# Ebook_Anita_Ghita.net
KiCad netlist of a schematic drawn in EAGLE
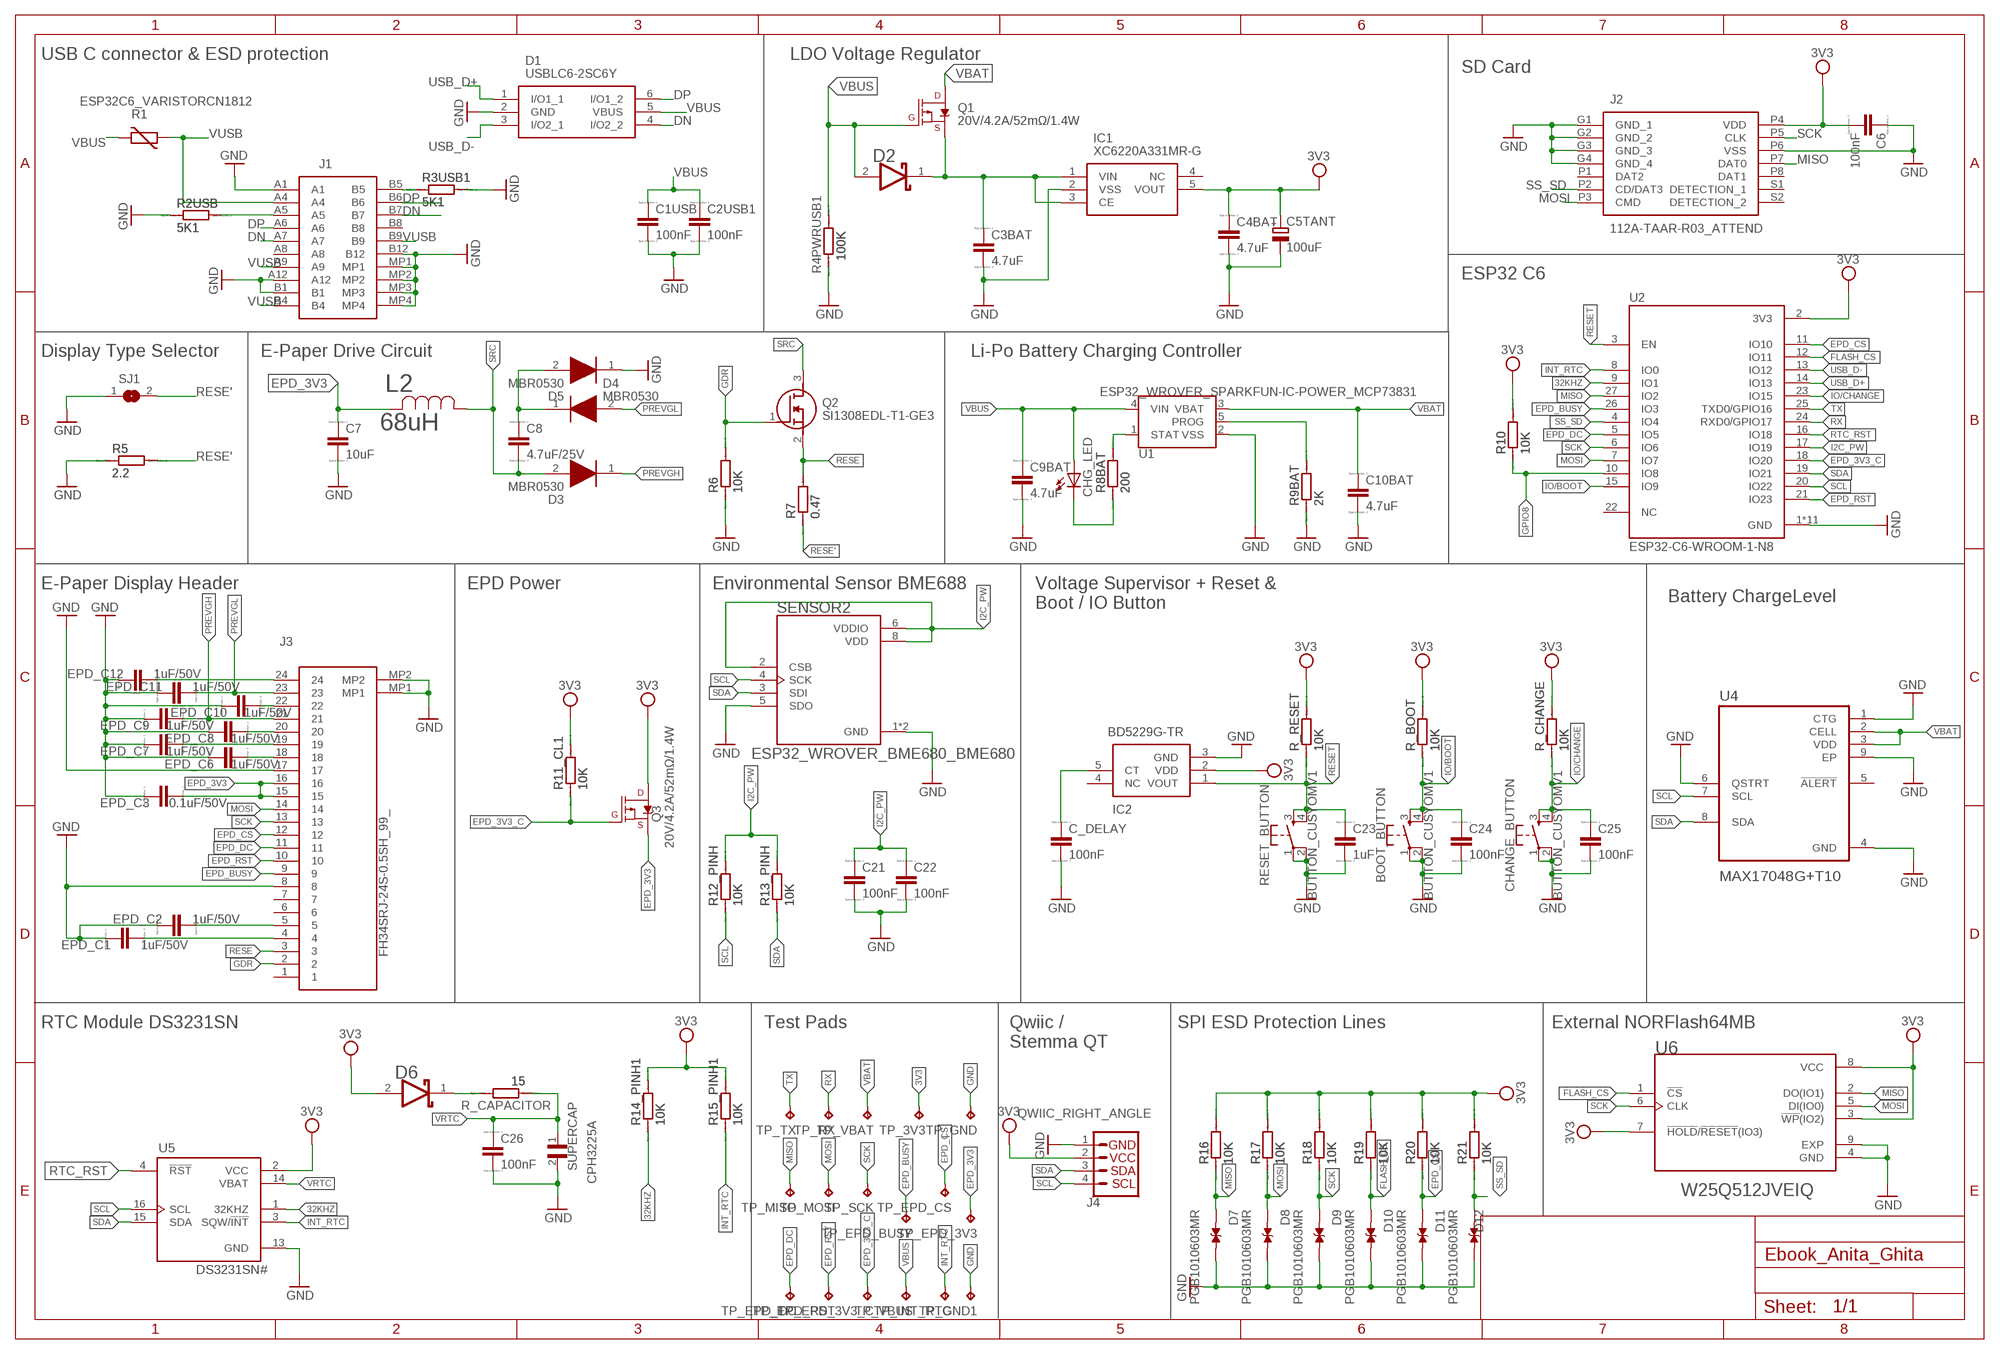
[diagram p0: schematic, sheet 1]

(export (version "E")
  (design (tool "Eeschema 10.0.6"))
  (components
    (comp (ref "BOOT_BUTTON")
      (value "BUTTON_CUSYOMV1")
      (footprint "eagle-import:MYBUTTON")
      (libsource (lib "eagle-import") (part "BUTTON_CUSYOMV1"))
    )
    (comp (ref "C1USB")
      (value "100nF")
      (footprint "eagle-import:ESP32_WROVER_EAGLE-LTSPICE_C0402")
      (libsource (lib "eagle-import") (part "EAGLE-LTSPICE_CC0402"))
    )
    (comp (ref "C2USB1")
      (value "100nF")
      (footprint "eagle-import:ESP32_WROVER_EAGLE-LTSPICE_C0402")
      (libsource (lib "eagle-import") (part "EAGLE-LTSPICE_CC0402"))
    )
    (comp (ref "C3BAT")
      (value "4.7uF")
      (footprint "eagle-import:ESP32_WROVER_EAGLE-LTSPICE_C0402")
      (libsource (lib "eagle-import") (part "EAGLE-LTSPICE_CC0402"))
    )
    (comp (ref "C4BAT")
      (value "4.7uF")
      (footprint "eagle-import:ESP32_WROVER_EAGLE-LTSPICE_C0402")
      (libsource (lib "eagle-import") (part "EAGLE-LTSPICE_CC0402"))
    )
    (comp (ref "C5TANT")
      (value "100uF")
      (footprint "eagle-import:RCL_CT3528")
      (libsource (lib "eagle-import") (part "RCL_CPOL-EUCT3528"))
    )
    (comp (ref "C6")
      (value "100nF")
      (footprint "eagle-import:ESP32_WROVER_EAGLE-LTSPICE_C0402")
      (libsource (lib "eagle-import") (part "EAGLE-LTSPICE_CC0402"))
    )
    (comp (ref "C7")
      (value "10uF")
      (footprint "eagle-import:ESP32_WROVER_EAGLE-LTSPICE_C0402")
      (libsource (lib "eagle-import") (part "EAGLE-LTSPICE_CC0402"))
    )
    (comp (ref "C8")
      (value "4.7uF/25V")
      (footprint "eagle-import:ESP32_WROVER_EAGLE-LTSPICE_C0402")
      (libsource (lib "eagle-import") (part "EAGLE-LTSPICE_CC0402"))
    )
    (comp (ref "C9BAT")
      (value "4.7uF")
      (footprint "eagle-import:ESP32_WROVER_EAGLE-LTSPICE_C0402")
      (libsource (lib "eagle-import") (part "EAGLE-LTSPICE_CC0402"))
    )
    (comp (ref "C10BAT")
      (value "4.7uF")
      (footprint "eagle-import:ESP32_WROVER_EAGLE-LTSPICE_C0402")
      (libsource (lib "eagle-import") (part "EAGLE-LTSPICE_CC0402"))
    )
    (comp (ref "C21")
      (value "100nF")
      (footprint "eagle-import:ESP32_WROVER_EAGLE-LTSPICE_C0402")
      (libsource (lib "eagle-import") (part "EAGLE-LTSPICE_CC0402"))
    )
    (comp (ref "C22")
      (value "100nF")
      (footprint "eagle-import:ESP32_WROVER_EAGLE-LTSPICE_C0402")
      (libsource (lib "eagle-import") (part "EAGLE-LTSPICE_CC0402"))
    )
    (comp (ref "C23")
      (value "1uF")
      (footprint "eagle-import:ESP32_WROVER_EAGLE-LTSPICE_C0402")
      (libsource (lib "eagle-import") (part "EAGLE-LTSPICE_CC0402"))
    )
    (comp (ref "C24")
      (value "100nF")
      (footprint "eagle-import:ESP32_WROVER_EAGLE-LTSPICE_C0402")
      (libsource (lib "eagle-import") (part "EAGLE-LTSPICE_CC0402"))
    )
    (comp (ref "C25")
      (value "100nF")
      (footprint "eagle-import:ESP32_WROVER_EAGLE-LTSPICE_C0402")
      (libsource (lib "eagle-import") (part "EAGLE-LTSPICE_CC0402"))
    )
    (comp (ref "C26")
      (value "100nF")
      (footprint "eagle-import:ESP32_WROVER_EAGLE-LTSPICE_C0402")
      (libsource (lib "eagle-import") (part "EAGLE-LTSPICE_CC0402"))
    )
    (comp (ref "CHANGE_BUTTON")
      (value "BUTTON_CUSYOMV1")
      (footprint "eagle-import:MYBUTTON")
      (libsource (lib "eagle-import") (part "BUTTON_CUSYOMV1"))
    )
    (comp (ref "CHG_LED")
      (value "ADAFRUIT_LEDCHIP-LED0603")
      (footprint "eagle-import:ADAFRUIT_CHIP-LED0603")
      (libsource (lib "eagle-import") (part "ADAFRUIT_LEDCHIP-LED0603"))
    )
    (comp (ref "C_DELAY")
      (value "100nF")
      (footprint "eagle-import:ESP32_WROVER_EAGLE-LTSPICE_C0402")
      (libsource (lib "eagle-import") (part "EAGLE-LTSPICE_CC0402"))
    )
    (comp (ref "D1")
      (value "USBLC6-2SC6Y")
      (footprint "eagle-import:SOT95P280X145-6N")
      (fields (field (name "MF") "STMicroelectronics"))
      (libsource (lib "eagle-import") (part "USBLC6-2SC6Y"))
    )
    (comp (ref "D2")
      (value "ESP32_WROVER_AVX---SD0805S020S1R0_AVX_SD0805S020S1R0_0_0AVX_SD0805S020S1R0_0_0")
      (footprint "eagle-import:ESP32_WROVER_AVX---SD0805S020S1R0_AVX_SD0805S020S1R0_0")
      (fields
        (field (name "DIGIKEY_PART_NUMBER") "478-7800-1-ND")
        (field (name "MF") "AVX")
        (field (name "MOUSER_PART_NUMBER") "581-SD0805S020S1R0")
      )
      (libsource (lib "eagle-import") (part "ESP32_WROVER_AVX---SD0805S020S1R0_AVX_SD0805S020S1R0_0_0AVX_SD0805S020S1R0_0_0"))
    )
    (comp (ref "D3")
      (value "MBR0530")
      (footprint "eagle-import:SOD3716X135N")
      (fields (field (name "MF") "ON Semiconductor"))
      (libsource (lib "eagle-import") (part "MBR0530"))
    )
    (comp (ref "D4")
      (value "MBR0530")
      (footprint "eagle-import:SOD3716X135N")
      (fields (field (name "MF") "ON Semiconductor"))
      (libsource (lib "eagle-import") (part "MBR0530"))
    )
    (comp (ref "D5")
      (value "MBR0530")
      (footprint "eagle-import:SOD3716X135N")
      (fields (field (name "MF") "ON Semiconductor"))
      (libsource (lib "eagle-import") (part "MBR0530"))
    )
    (comp (ref "D6")
      (value "ESP32_WROVER_AVX---SD0805S020S1R0_AVX_SD0805S020S1R0_0_0AVX_SD0805S020S1R0_0_0")
      (footprint "eagle-import:ESP32_WROVER_AVX---SD0805S020S1R0_AVX_SD0805S020S1R0_0")
      (fields
        (field (name "DIGIKEY_PART_NUMBER") "478-7800-1-ND")
        (field (name "MF") "AVX")
        (field (name "MOUSER_PART_NUMBER") "581-SD0805S020S1R0")
      )
      (libsource (lib "eagle-import") (part "ESP32_WROVER_AVX---SD0805S020S1R0_AVX_SD0805S020S1R0_0_0AVX_SD0805S020S1R0_0_0"))
    )
    (comp (ref "D7")
      (value "PGB1010603MR")
      (footprint "eagle-import:DIOC1608X36N")
      (fields (field (name "MF") "Littelfuse Inc."))
      (libsource (lib "eagle-import") (part "PGB1010603MR"))
    )
    (comp (ref "D8")
      (value "PGB1010603MR")
      (footprint "eagle-import:DIOC1608X36N")
      (fields (field (name "MF") "Littelfuse Inc."))
      (libsource (lib "eagle-import") (part "PGB1010603MR"))
    )
    (comp (ref "D9")
      (value "PGB1010603MR")
      (footprint "eagle-import:DIOC1608X36N")
      (fields (field (name "MF") "Littelfuse Inc."))
      (libsource (lib "eagle-import") (part "PGB1010603MR"))
    )
    (comp (ref "D10")
      (value "PGB1010603MR")
      (footprint "eagle-import:DIOC1608X36N")
      (fields (field (name "MF") "Littelfuse Inc."))
      (libsource (lib "eagle-import") (part "PGB1010603MR"))
    )
    (comp (ref "D11")
      (value "PGB1010603MR")
      (footprint "eagle-import:DIOC1608X36N")
      (fields (field (name "MF") "Littelfuse Inc."))
      (libsource (lib "eagle-import") (part "PGB1010603MR"))
    )
    (comp (ref "D12")
      (value "PGB1010603MR")
      (footprint "eagle-import:DIOC1608X36N")
      (fields (field (name "MF") "Littelfuse Inc."))
      (libsource (lib "eagle-import") (part "PGB1010603MR"))
    )
    (comp (ref "EPD_C1")
      (value "1uF/50V")
      (footprint "eagle-import:ESP32_WROVER_EAGLE-LTSPICE_C0402")
      (libsource (lib "eagle-import") (part "EAGLE-LTSPICE_CC0402"))
    )
    (comp (ref "EPD_C2")
      (value "1uF/50V")
      (footprint "eagle-import:ESP32_WROVER_EAGLE-LTSPICE_C0402")
      (libsource (lib "eagle-import") (part "EAGLE-LTSPICE_CC0402"))
    )
    (comp (ref "EPD_C3")
      (value "0.1uF/50V")
      (footprint "eagle-import:ESP32_WROVER_EAGLE-LTSPICE_C0402")
      (libsource (lib "eagle-import") (part "EAGLE-LTSPICE_CC0402"))
    )
    (comp (ref "EPD_C6")
      (value "1uF/50V")
      (footprint "eagle-import:ESP32_WROVER_EAGLE-LTSPICE_C0402")
      (libsource (lib "eagle-import") (part "EAGLE-LTSPICE_CC0402"))
    )
    (comp (ref "EPD_C7")
      (value "1uF/50V")
      (footprint "eagle-import:ESP32_WROVER_EAGLE-LTSPICE_C0402")
      (libsource (lib "eagle-import") (part "EAGLE-LTSPICE_CC0402"))
    )
    (comp (ref "EPD_C8")
      (value "1uF/50V")
      (footprint "eagle-import:ESP32_WROVER_EAGLE-LTSPICE_C0402")
      (libsource (lib "eagle-import") (part "EAGLE-LTSPICE_CC0402"))
    )
    (comp (ref "EPD_C9")
      (value "1uF/50V")
      (footprint "eagle-import:ESP32_WROVER_EAGLE-LTSPICE_C0402")
      (libsource (lib "eagle-import") (part "EAGLE-LTSPICE_CC0402"))
    )
    (comp (ref "EPD_C10")
      (value "1uF/50V")
      (footprint "eagle-import:ESP32_WROVER_EAGLE-LTSPICE_C0402")
      (libsource (lib "eagle-import") (part "EAGLE-LTSPICE_CC0402"))
    )
    (comp (ref "EPD_C11")
      (value "1uF/50V")
      (footprint "eagle-import:ESP32_WROVER_EAGLE-LTSPICE_C0402")
      (libsource (lib "eagle-import") (part "EAGLE-LTSPICE_CC0402"))
    )
    (comp (ref "EPD_C12")
      (value "1uF/50V")
      (footprint "eagle-import:ESP32_WROVER_EAGLE-LTSPICE_C0402")
      (libsource (lib "eagle-import") (part "EAGLE-LTSPICE_CC0402"))
    )
    (comp (ref "IC1")
      (value "XC6220A331MR-G")
      (footprint "eagle-import:SOT95P280X120-5N")
      (fields (field (name "MOUSER_PART_NUMBER") "865-XC6220A331MR-G"))
      (libsource (lib "eagle-import") (part "XC6220A331MR-G"))
    )
    (comp (ref "IC2")
      (value "BD5229G-TR")
      (footprint "eagle-import:SOT95P280X125-5N")
      (fields (field (name "MOUSER_PART_NUMBER") "755-BD5229G-TR"))
      (libsource (lib "eagle-import") (part "BD5229G-TR"))
    )
    (comp (ref "J1")
      (value "SAMACSYS_PARTS_USB4110-GF-A")
      (footprint "eagle-import:SAMACSYS_PARTS_USB4110GFA")
      (fields
        (field (name "MANUFACTURER_PART_NUMBER") "USB4110-GF-A")
        (field (name "MOUSER_PART_NUMBER") "640-USB4110-GF-A")
      )
      (libsource (lib "eagle-import") (part "SAMACSYS_PARTS_USB4110-GF-A"))
    )
    (comp (ref "J2")
      (value "112A-TAAR-R03_ATTEND")
      (footprint "eagle-import:112ATAARR03ATTEND")
      (fields (field (name "MANUFACTURER_PART_NUMBER") "112A-TAAR-R03 ATTEND"))
      (libsource (lib "eagle-import") (part "112A-TAAR-R03_ATTEND"))
    )
    (comp (ref "J3")
      (value "FH34SRJ-24S-0.5SH_99_")
      (footprint "eagle-import:FH34SRJ24S05SH99")
      (fields
        (field (name "MANUFACTURER_PART_NUMBER") "FH34SRJ-24S-0.5SH(99)")
        (field (name "MOUSER_PART_NUMBER") "798-FH34SRJ24S05SH99")
      )
      (libsource (lib "eagle-import") (part "FH34SRJ-24S-0.5SH_99_"))
    )
    (comp (ref "J4")
      (value "QWIIC_RIGHT_ANGLE")
      (footprint "eagle-import:JST04_1MM_RA")
      (libsource (lib "eagle-import") (part "QWIIC_CONNECTORJS-1MM"))
    )
    (comp (ref "L2")
      (value "68uH")
      (footprint "eagle-import:IND_4828-WE-TPC_WRE")
      (fields
        (field (name "MANUFACTURER_PART_NUMBER") "744043680")
        (field (name "COPYRIGHT") "Copyright (C) 2024 Ultra Librarian. All rights reserved.")
      )
      (libsource (lib "eagle-import") (part "744043680IND_4828-WE-TPC_WRE"))
    )
    (comp (ref "Q1")
      (value "20V/4.2A/52mΩ/1.4W")
      (footprint "eagle-import:ESP32_WROVER_SPARKFUN-DISCRETESEMI_SOT23-3")
      (libsource (lib "eagle-import") (part "ESP32_WROVER_SPARKFUN-DISCRETESEMI_MOSFET_PCH-DMG2305UX-7"))
    )
    (comp (ref "Q2")
      (value "SI1308EDL-T1-GE3")
      (footprint "eagle-import:SOT65P210X110-3N")
      (fields (field (name "MF") "Vishay Siliconix"))
      (libsource (lib "eagle-import") (part "SI1308EDL-T1-GE3"))
    )
    (comp (ref "Q3")
      (value "20V/4.2A/52mΩ/1.4W")
      (footprint "eagle-import:ESP32_WROVER_SPARKFUN-DISCRETESEMI_SOT23-3")
      (libsource (lib "eagle-import") (part "ESP32_WROVER_SPARKFUN-DISCRETESEMI_MOSFET_PCH-DMG2305UX-7"))
    )
    (comp (ref "R1")
      (value "ESP32C6_VARISTORCN1812")
      (footprint "eagle-import:ESP32C6_VARISTOR_CT_CN1812")
      (libsource (lib "eagle-import") (part "ESP32C6_VARISTORCN1812"))
    )
    (comp (ref "R2USB")
      (value "5K1")
      (footprint "eagle-import:ESP32_WROVER_EAGLE-LTSPICE_R0402")
      (libsource (lib "eagle-import") (part "ESP32_WROVER_EAGLE-LTSPICE_RR0402"))
    )
    (comp (ref "R3USB1")
      (value "5K1")
      (footprint "eagle-import:ESP32_WROVER_EAGLE-LTSPICE_R0402")
      (libsource (lib "eagle-import") (part "ESP32_WROVER_EAGLE-LTSPICE_RR0402"))
    )
    (comp (ref "R4PWRUSB1")
      (value "100K")
      (footprint "eagle-import:ESP32_WROVER_EAGLE-LTSPICE_R0402")
      (libsource (lib "eagle-import") (part "ESP32_WROVER_EAGLE-LTSPICE_RR0402"))
    )
    (comp (ref "R5")
      (value "2.2")
      (footprint "eagle-import:ESP32_WROVER_EAGLE-LTSPICE_R0402")
      (libsource (lib "eagle-import") (part "ESP32_WROVER_EAGLE-LTSPICE_RR0402"))
    )
    (comp (ref "R6")
      (value "10K")
      (footprint "eagle-import:ESP32_WROVER_EAGLE-LTSPICE_R0402")
      (libsource (lib "eagle-import") (part "ESP32_WROVER_EAGLE-LTSPICE_RR0402"))
    )
    (comp (ref "R7")
      (value "0.47")
      (footprint "eagle-import:ESP32_WROVER_EAGLE-LTSPICE_R0402")
      (libsource (lib "eagle-import") (part "ESP32_WROVER_EAGLE-LTSPICE_RR0402"))
    )
    (comp (ref "R8BAT")
      (value "200")
      (footprint "eagle-import:ESP32_WROVER_EAGLE-LTSPICE_R0402")
      (libsource (lib "eagle-import") (part "ESP32_WROVER_EAGLE-LTSPICE_RR0402"))
    )
    (comp (ref "R9BAT")
      (value "2K")
      (footprint "eagle-import:ESP32_WROVER_EAGLE-LTSPICE_R0402")
      (libsource (lib "eagle-import") (part "ESP32_WROVER_EAGLE-LTSPICE_RR0402"))
    )
    (comp (ref "R10")
      (value "10K")
      (footprint "eagle-import:ESP32_WROVER_EAGLE-LTSPICE_R0402")
      (libsource (lib "eagle-import") (part "ESP32_WROVER_EAGLE-LTSPICE_RR0402"))
    )
    (comp (ref "R11_CL1")
      (value "10K")
      (footprint "eagle-import:ESP32_WROVER_EAGLE-LTSPICE_R0402")
      (libsource (lib "eagle-import") (part "ESP32_WROVER_EAGLE-LTSPICE_RR0402"))
    )
    (comp (ref "R12_PINH")
      (value "10K")
      (footprint "eagle-import:ESP32_WROVER_EAGLE-LTSPICE_R0402")
      (libsource (lib "eagle-import") (part "ESP32_WROVER_EAGLE-LTSPICE_RR0402"))
    )
    (comp (ref "R13_PINH")
      (value "10K")
      (footprint "eagle-import:ESP32_WROVER_EAGLE-LTSPICE_R0402")
      (libsource (lib "eagle-import") (part "ESP32_WROVER_EAGLE-LTSPICE_RR0402"))
    )
    (comp (ref "R14_PINH1")
      (value "10K")
      (footprint "eagle-import:ESP32_WROVER_EAGLE-LTSPICE_R0402")
      (libsource (lib "eagle-import") (part "ESP32_WROVER_EAGLE-LTSPICE_RR0402"))
    )
    (comp (ref "R15_PINH1")
      (value "10K")
      (footprint "eagle-import:ESP32_WROVER_EAGLE-LTSPICE_R0402")
      (libsource (lib "eagle-import") (part "ESP32_WROVER_EAGLE-LTSPICE_RR0402"))
    )
    (comp (ref "R16")
      (value "10K")
      (footprint "eagle-import:ESP32_WROVER_EAGLE-LTSPICE_R0402")
      (libsource (lib "eagle-import") (part "ESP32_WROVER_EAGLE-LTSPICE_RR0402"))
    )
    (comp (ref "R17")
      (value "10K")
      (footprint "eagle-import:ESP32_WROVER_EAGLE-LTSPICE_R0402")
      (libsource (lib "eagle-import") (part "ESP32_WROVER_EAGLE-LTSPICE_RR0402"))
    )
    (comp (ref "R18")
      (value "10K")
      (footprint "eagle-import:ESP32_WROVER_EAGLE-LTSPICE_R0402")
      (libsource (lib "eagle-import") (part "ESP32_WROVER_EAGLE-LTSPICE_RR0402"))
    )
    (comp (ref "R19")
      (value "10K")
      (footprint "eagle-import:ESP32_WROVER_EAGLE-LTSPICE_R0402")
      (libsource (lib "eagle-import") (part "ESP32_WROVER_EAGLE-LTSPICE_RR0402"))
    )
    (comp (ref "R20")
      (value "10K")
      (footprint "eagle-import:ESP32_WROVER_EAGLE-LTSPICE_R0402")
      (libsource (lib "eagle-import") (part "ESP32_WROVER_EAGLE-LTSPICE_RR0402"))
    )
    (comp (ref "R21")
      (value "10K")
      (footprint "eagle-import:ESP32_WROVER_EAGLE-LTSPICE_R0402")
      (libsource (lib "eagle-import") (part "ESP32_WROVER_EAGLE-LTSPICE_RR0402"))
    )
    (comp (ref "RESET_BUTTON")
      (value "BUTTON_CUSYOMV1")
      (footprint "eagle-import:MYBUTTON")
      (libsource (lib "eagle-import") (part "BUTTON_CUSYOMV1"))
    )
    (comp (ref "R_BOOT")
      (value "10K")
      (footprint "eagle-import:ESP32_WROVER_EAGLE-LTSPICE_R0402")
      (libsource (lib "eagle-import") (part "ESP32_WROVER_EAGLE-LTSPICE_RR0402"))
    )
    (comp (ref "R_CAPACITOR")
      (value "15")
      (footprint "eagle-import:ESP32_WROVER_EAGLE-LTSPICE_R0402")
      (libsource (lib "eagle-import") (part "ESP32_WROVER_EAGLE-LTSPICE_RR0402"))
    )
    (comp (ref "R_CHANGE")
      (value "10K")
      (footprint "eagle-import:ESP32_WROVER_EAGLE-LTSPICE_R0402")
      (libsource (lib "eagle-import") (part "ESP32_WROVER_EAGLE-LTSPICE_RR0402"))
    )
    (comp (ref "R_RESET")
      (value "10K")
      (footprint "eagle-import:ESP32_WROVER_EAGLE-LTSPICE_R0402")
      (libsource (lib "eagle-import") (part "ESP32_WROVER_EAGLE-LTSPICE_RR0402"))
    )
    (comp (ref "SENSOR2")
      (value "ESP32_WROVER_BME680_BME680")
      (footprint "eagle-import:ESP32_WROVER_BME680_PSON80P300X300X100-8N")
      (fields (field (name "MF") "Bosch Sensortec") (field (name "MP") "BME680"))
      (libsource (lib "eagle-import") (part "ESP32_WROVER_BME680_BME680"))
    )
    (comp (ref "SJ1") (value "SJ") (footprint "eagle-import:SJ") (libsource (lib "eagle-import") (part "SJ")))
    (comp (ref "SUPERCAP")
      (value "CPH3225A")
      (footprint "eagle-import:CAPCP3225X100N")
      (fields (field (name "MF") "Seiko Instruments"))
      (libsource (lib "eagle-import") (part "CPH3225A"))
    )
    (comp (ref "TP_3V3")
      (value "TPTP20R")
      (footprint "eagle-import:TP20R")
      (libsource (lib "eagle-import") (part "TPTP20R"))
    )
    (comp (ref "TP_EPD_3V3")
      (value "TPTP20R")
      (footprint "eagle-import:TP20R")
      (libsource (lib "eagle-import") (part "TPTP20R"))
    )
    (comp (ref "TP_EPD_3V3_C")
      (value "TPTP20R")
      (footprint "eagle-import:TP20R")
      (libsource (lib "eagle-import") (part "TPTP20R"))
    )
    (comp (ref "TP_EPD_BUSY")
      (value "TPTP20R")
      (footprint "eagle-import:TP20R")
      (libsource (lib "eagle-import") (part "TPTP20R"))
    )
    (comp (ref "TP_EPD_CS")
      (value "TPTP20R")
      (footprint "eagle-import:TP20R")
      (libsource (lib "eagle-import") (part "TPTP20R"))
    )
    (comp (ref "TP_EPD_DC")
      (value "TPTP20R")
      (footprint "eagle-import:TP20R")
      (libsource (lib "eagle-import") (part "TPTP20R"))
    )
    (comp (ref "TP_EPD_RST")
      (value "TPTP20R")
      (footprint "eagle-import:TP20R")
      (libsource (lib "eagle-import") (part "TPTP20R"))
    )
    (comp (ref "TP_GND")
      (value "TPTP20R")
      (footprint "eagle-import:TP20R")
      (libsource (lib "eagle-import") (part "TPTP20R"))
    )
    (comp (ref "TP_GND1")
      (value "TPTP20R")
      (footprint "eagle-import:TP20R")
      (libsource (lib "eagle-import") (part "TPTP20R"))
    )
    (comp (ref "TP_INT_RTC")
      (value "TPTP20R")
      (footprint "eagle-import:TP20R")
      (libsource (lib "eagle-import") (part "TPTP20R"))
    )
    (comp (ref "TP_MISO")
      (value "TPTP20R")
      (footprint "eagle-import:TP20R")
      (libsource (lib "eagle-import") (part "TPTP20R"))
    )
    (comp (ref "TP_MOSI")
      (value "TPTP20R")
      (footprint "eagle-import:TP20R")
      (libsource (lib "eagle-import") (part "TPTP20R"))
    )
    (comp (ref "TP_RX")
      (value "TPTP20R")
      (footprint "eagle-import:TP20R")
      (libsource (lib "eagle-import") (part "TPTP20R"))
    )
    (comp (ref "TP_SCK")
      (value "TPTP20R")
      (footprint "eagle-import:TP20R")
      (libsource (lib "eagle-import") (part "TPTP20R"))
    )
    (comp (ref "TP_TX")
      (value "TPTP20R")
      (footprint "eagle-import:TP20R")
      (libsource (lib "eagle-import") (part "TPTP20R"))
    )
    (comp (ref "TP_VBAT")
      (value "TPTP20R")
      (footprint "eagle-import:TP20R")
      (libsource (lib "eagle-import") (part "TPTP20R"))
    )
    (comp (ref "TP_VBUS")
      (value "TPTP20R")
      (footprint "eagle-import:TP20R")
      (libsource (lib "eagle-import") (part "TPTP20R"))
    )
    (comp (ref "U1")
      (value "ESP32_WROVER_SPARKFUN-IC-POWER_MCP73831")
      (footprint "eagle-import:ESP32_WROVER_SPARKFUN-IC-POWER_SOT23-5")
      (libsource (lib "eagle-import") (part "ESP32_WROVER_SPARKFUN-IC-POWER_MCP73831"))
    )
    (comp (ref "U2")
      (value "ESP32-C6-WROOM-1-N8")
      (footprint "eagle-import:XCVR_ESP32-C6-WROOM-1-N8")
      (fields (field (name "MF") "Espressif Systems"))
      (libsource (lib "eagle-import") (part "ESP32-C6-WROOM-1-N8"))
    )
    (comp (ref "U4")
      (value "MAX17048G+T10")
      (footprint "eagle-import:SON50P200X200X80-9N")
      (fields (field (name "MF") "Analog Devices"))
      (libsource (lib "eagle-import") (part "MAX17048G+T10"))
    )
    (comp (ref "U5")
      (value "DS3231SN#")
      (footprint "eagle-import:SOIC127P1032X265-16N")
      (fields (field (name "MF") "Analog Devices"))
      (libsource (lib "eagle-import") (part "DS3231SN#"))
    )
    (comp (ref "U6")
      (value "W25Q512JVEIQ")
      (footprint "eagle-import:SON127P600X800X80-9N")
      (fields (field (name "MF") "Winbond Electronics"))
      (libsource (lib "eagle-import") (part "W25Q512JVEIQ"))
    )
  )
  (nets
    (net (code "1") (name "/DN") (class "Default")
      (node (ref "D1") (pin "4") (pinfunction "I/O2_2_4") (pintype "bidirectional"))
      (node (ref "J1") (pin "A7") (pinfunction "A7_A7") (pintype "bidirectional"))
      (node (ref "J1") (pin "B7") (pinfunction "B7_B7") (pintype "bidirectional"))
    )
    (net (code "2") (name "/DP") (class "Default")
      (node (ref "D1") (pin "6") (pinfunction "I/O1_2_6") (pintype "bidirectional"))
      (node (ref "J1") (pin "A6") (pinfunction "A6_A6") (pintype "bidirectional"))
      (node (ref "J1") (pin "B6") (pinfunction "B6_B6") (pintype "bidirectional"))
    )
    (net (code "3") (name "/VUSB") (class "Default")
      (node (ref "J1") (pin "A4") (pinfunction "A4_A4") (pintype "bidirectional"))
      (node (ref "J1") (pin "A9") (pinfunction "A9_A9") (pintype "bidirectional"))
      (node (ref "J1") (pin "B4") (pinfunction "B4_B4") (pintype "bidirectional"))
      (node (ref "J1") (pin "B9") (pinfunction "B9_B9") (pintype "bidirectional"))
      (node (ref "R1") (pin "1") (pinfunction "1_1") (pintype "passive"))
    )
    (net (code "4") (name "3V3") (class "Default")
      (node (ref "C4BAT") (pin "1") (pinfunction "1_1") (pintype "passive"))
      (node (ref "C5TANT") (pin "+") (pinfunction "+_+") (pintype "passive"))
      (node (ref "C6") (pin "2") (pinfunction "2_2") (pintype "passive"))
      (node (ref "D6") (pin "2") (pinfunction "ANODE_2") (pintype "bidirectional"))
      (node (ref "IC1") (pin "5") (pinfunction "VOUT_5") (pintype "bidirectional"))
      (node (ref "IC2") (pin "2") (pinfunction "VDD_2") (pintype "bidirectional"))
      (node (ref "J2") (pin "P4") (pinfunction "VDD_P4") (pintype "bidirectional"))
      (node (ref "J4") (pin "2") (pinfunction "2_2") (pintype "power_in"))
      (node (ref "Q3") (pin "3") (pinfunction "D_3") (pintype "bidirectional"))
      (node (ref "R10") (pin "2") (pinfunction "2_2") (pintype "passive"))
      (node (ref "R11_CL1") (pin "2") (pinfunction "2_2") (pintype "passive"))
      (node (ref "R14_PINH1") (pin "2") (pinfunction "2_2") (pintype "passive"))
      (node (ref "R15_PINH1") (pin "2") (pinfunction "2_2") (pintype "passive"))
      (node (ref "R16") (pin "2") (pinfunction "2_2") (pintype "passive"))
      (node (ref "R17") (pin "2") (pinfunction "2_2") (pintype "passive"))
      (node (ref "R18") (pin "2") (pinfunction "2_2") (pintype "passive"))
      (node (ref "R19") (pin "2") (pinfunction "2_2") (pintype "passive"))
      (node (ref "R20") (pin "2") (pinfunction "2_2") (pintype "passive"))
      (node (ref "R21") (pin "2") (pinfunction "2_2") (pintype "passive"))
      (node (ref "R_BOOT") (pin "2") (pinfunction "2_2") (pintype "passive"))
      (node (ref "R_CHANGE") (pin "2") (pinfunction "2_2") (pintype "passive"))
      (node (ref "R_RESET") (pin "2") (pinfunction "2_2") (pintype "passive"))
      (node (ref "TP_3V3") (pin "TP") (pinfunction "TP_TP") (pintype "input"))
      (node (ref "U2") (pin "2") (pinfunction "3V3_2") (pintype "power_in"))
      (node (ref "U5") (pin "2") (pinfunction "VCC_2") (pintype "power_in"))
      (node (ref "U6") (pin "3") (pinfunction "~{WP}(IO2)_3") (pintype "bidirectional"))
      (node (ref "U6") (pin "7") (pinfunction "~{HOLD}/~{RESET}(IO3)_7") (pintype "bidirectional"))
      (node (ref "U6") (pin "8") (pinfunction "VCC_8") (pintype "power_in"))
    )
    (net (code "5") (name "32KHZ") (class "Default")
      (node (ref "R14_PINH1") (pin "1") (pinfunction "1_1") (pintype "passive"))
      (node (ref "U2") (pin "9") (pinfunction "IO1_9") (pintype "bidirectional"))
      (node (ref "U5") (pin "1") (pinfunction "32KHZ_1") (pintype "output"))
    )
    (net (code "6") (name "EPD_3V3") (class "Default")
      (node (ref "C7") (pin "1") (pinfunction "1_1") (pintype "passive"))
      (node (ref "EPD_C3") (pin "2") (pinfunction "2_2") (pintype "passive"))
      (node (ref "J3") (pin "15") (pinfunction "15_15") (pintype "bidirectional"))
      (node (ref "J3") (pin "16") (pinfunction "16_16") (pintype "bidirectional"))
      (node (ref "L2") (pin "2") (pinfunction "2_2") (pintype "passive"))
      (node (ref "Q3") (pin "2") (pinfunction "S_2") (pintype "bidirectional"))
      (node (ref "TP_EPD_3V3") (pin "TP") (pinfunction "TP_TP") (pintype "input"))
    )
    (net (code "7") (name "EPD_3V3_C") (class "Default")
      (node (ref "Q3") (pin "1") (pinfunction "G_1") (pintype "bidirectional"))
      (node (ref "R11_CL1") (pin "1") (pinfunction "1_1") (pintype "passive"))
      (node (ref "TP_EPD_3V3_C") (pin "TP") (pinfunction "TP_TP") (pintype "input"))
      (node (ref "U2") (pin "18") (pinfunction "IO20_18") (pintype "bidirectional"))
    )
    (net (code "8") (name "EPD_BUSY") (class "Default")
      (node (ref "J3") (pin "9") (pinfunction "9_9") (pintype "bidirectional"))
      (node (ref "TP_EPD_BUSY") (pin "TP") (pinfunction "TP_TP") (pintype "input"))
      (node (ref "U2") (pin "26") (pinfunction "IO3_26") (pintype "bidirectional"))
    )
    (net (code "9") (name "EPD_CS") (class "Default")
      (node (ref "D11") (pin "1") (pinfunction "1_1") (pintype "passive"))
      (node (ref "J3") (pin "12") (pinfunction "12_12") (pintype "bidirectional"))
      (node (ref "R20") (pin "1") (pinfunction "1_1") (pintype "passive"))
      (node (ref "TP_EPD_CS") (pin "TP") (pinfunction "TP_TP") (pintype "input"))
      (node (ref "U2") (pin "11") (pinfunction "IO10_11") (pintype "bidirectional"))
    )
    (net (code "10") (name "EPD_DC") (class "Default")
      (node (ref "J3") (pin "11") (pinfunction "11_11") (pintype "bidirectional"))
      (node (ref "TP_EPD_DC") (pin "TP") (pinfunction "TP_TP") (pintype "input"))
      (node (ref "U2") (pin "5") (pinfunction "IO5_5") (pintype "bidirectional"))
    )
    (net (code "11") (name "EPD_RST") (class "Default")
      (node (ref "J3") (pin "10") (pinfunction "10_10") (pintype "bidirectional"))
      (node (ref "TP_EPD_RST") (pin "TP") (pinfunction "TP_TP") (pintype "input"))
      (node (ref "U2") (pin "21") (pinfunction "IO23_21") (pintype "bidirectional"))
    )
    (net (code "12") (name "FLASH_CS") (class "Default")
      (node (ref "D10") (pin "1") (pinfunction "1_1") (pintype "passive"))
      (node (ref "R19") (pin "1") (pinfunction "1_1") (pintype "passive"))
      (node (ref "U2") (pin "12") (pinfunction "IO11_12") (pintype "bidirectional"))
      (node (ref "U6") (pin "1") (pinfunction "~{CS}_1") (pintype "input"))
    )
    (net (code "13") (name "GDR") (class "Default")
      (node (ref "J3") (pin "2") (pinfunction "2_2") (pintype "bidirectional"))
      (node (ref "Q2") (pin "1") (pinfunction "G_1") (pintype "bidirectional"))
      (node (ref "R6") (pin "2") (pinfunction "2_2") (pintype "passive"))
    )
    (net (code "14") (name "GND") (class "Default")
      (node (ref "BOOT_BUTTON") (pin "1") (pinfunction "1_1") (pintype "passive"))
      (node (ref "BOOT_BUTTON") (pin "2") (pinfunction "2_2") (pintype "passive"))
      (node (ref "C10BAT") (pin "2") (pinfunction "2_2") (pintype "passive"))
      (node (ref "C1USB") (pin "2") (pinfunction "2_2") (pintype "passive"))
      (node (ref "C21") (pin "2") (pinfunction "2_2") (pintype "passive"))
      (node (ref "C22") (pin "2") (pinfunction "2_2") (pintype "passive"))
      (node (ref "C23") (pin "2") (pinfunction "2_2") (pintype "passive"))
      (node (ref "C24") (pin "2") (pinfunction "2_2") (pintype "passive"))
      (node (ref "C25") (pin "2") (pinfunction "2_2") (pintype "passive"))
      (node (ref "C26") (pin "2") (pinfunction "2_2") (pintype "passive"))
      (node (ref "C2USB1") (pin "2") (pinfunction "2_2") (pintype "passive"))
      (node (ref "C3BAT") (pin "2") (pinfunction "2_2") (pintype "passive"))
      (node (ref "C4BAT") (pin "2") (pinfunction "2_2") (pintype "passive"))
      (node (ref "C5TANT") (pin "-") (pinfunction "-_-") (pintype "passive"))
      (node (ref "C6") (pin "1") (pinfunction "1_1") (pintype "passive"))
      (node (ref "C7") (pin "2") (pinfunction "2_2") (pintype "passive"))
      (node (ref "C9BAT") (pin "2") (pinfunction "2_2") (pintype "passive"))
      (node (ref "CHANGE_BUTTON") (pin "1") (pinfunction "1_1") (pintype "passive"))
      (node (ref "CHANGE_BUTTON") (pin "2") (pinfunction "2_2") (pintype "passive"))
      (node (ref "C_DELAY") (pin "2") (pinfunction "2_2") (pintype "passive"))
      (node (ref "D1") (pin "2") (pinfunction "GND_2") (pintype "bidirectional"))
      (node (ref "D10") (pin "2") (pinfunction "2_2") (pintype "passive"))
      (node (ref "D11") (pin "2") (pinfunction "2_2") (pintype "passive"))
      (node (ref "D12") (pin "2") (pinfunction "2_2") (pintype "passive"))
      (node (ref "D5") (pin "1") (pinfunction "K_1") (pintype "bidirectional"))
      (node (ref "D7") (pin "2") (pinfunction "2_2") (pintype "passive"))
      (node (ref "D8") (pin "2") (pinfunction "2_2") (pintype "passive"))
      (node (ref "D9") (pin "2") (pinfunction "2_2") (pintype "passive"))
      (node (ref "EPD_C1") (pin "1") (pinfunction "1_1") (pintype "passive"))
      (node (ref "EPD_C10") (pin "1") (pinfunction "1_1") (pintype "passive"))
      (node (ref "EPD_C11") (pin "1") (pinfunction "1_1") (pintype "passive"))
      (node (ref "EPD_C12") (pin "1") (pinfunction "1_1") (pintype "passive"))
      (node (ref "EPD_C2") (pin "1") (pinfunction "1_1") (pintype "passive"))
      (node (ref "EPD_C3") (pin "1") (pinfunction "1_1") (pintype "passive"))
      (node (ref "EPD_C6") (pin "1") (pinfunction "1_1") (pintype "passive"))
      (node (ref "EPD_C7") (pin "1") (pinfunction "1_1") (pintype "passive"))
      (node (ref "EPD_C8") (pin "1") (pinfunction "1_1") (pintype "passive"))
      (node (ref "EPD_C9") (pin "1") (pinfunction "1_1") (pintype "passive"))
      (node (ref "IC1") (pin "2") (pinfunction "VSS_2") (pintype "bidirectional"))
      (node (ref "IC2") (pin "3") (pinfunction "GND_3") (pintype "bidirectional"))
      (node (ref "J1") (pin "A1") (pinfunction "A1_A1") (pintype "bidirectional"))
      (node (ref "J1") (pin "A12") (pinfunction "A12_A12") (pintype "bidirectional"))
      (node (ref "J1") (pin "B1") (pinfunction "B1_B1") (pintype "bidirectional"))
      (node (ref "J1") (pin "B12") (pinfunction "B12_B12") (pintype "bidirectional"))
      (node (ref "J1") (pin "MP1") (pinfunction "MP1_MP1") (pintype "bidirectional"))
      (node (ref "J1") (pin "MP2") (pinfunction "MP2_MP2") (pintype "bidirectional"))
      (node (ref "J1") (pin "MP3") (pinfunction "MP3_MP3") (pintype "bidirectional"))
      (node (ref "J1") (pin "MP4") (pinfunction "MP4_MP4") (pintype "bidirectional"))
      (node (ref "J2") (pin "G1") (pinfunction "GND_1_G1") (pintype "bidirectional"))
      (node (ref "J2") (pin "G2") (pinfunction "GND_2_G2") (pintype "bidirectional"))
      (node (ref "J2") (pin "G3") (pinfunction "GND_3_G3") (pintype "bidirectional"))
      (node (ref "J2") (pin "G4") (pinfunction "GND_4_G4") (pintype "bidirectional"))
      (node (ref "J2") (pin "P6") (pinfunction "VSS_P6") (pintype "bidirectional"))
      (node (ref "J3") (pin "17") (pinfunction "17_17") (pintype "bidirectional"))
      (node (ref "J3") (pin "8") (pinfunction "8_8") (pintype "bidirectional"))
      (node (ref "J3") (pin "MP1") (pinfunction "MP1_MP1") (pintype "bidirectional"))
      (node (ref "J3") (pin "MP2") (pinfunction "MP2_MP2") (pintype "bidirectional"))
      (node (ref "J4") (pin "1") (pinfunction "1_1") (pintype "power_in"))
      (node (ref "R2USB") (pin "1") (pinfunction "1_1") (pintype "passive"))
      (node (ref "R3USB1") (pin "2") (pinfunction "2_2") (pintype "passive"))
      (node (ref "R4PWRUSB1") (pin "1") (pinfunction "1_1") (pintype "passive"))
      (node (ref "R5") (pin "1") (pinfunction "1_1") (pintype "passive"))
      (node (ref "R6") (pin "1") (pinfunction "1_1") (pintype "passive"))
      (node (ref "R9BAT") (pin "1") (pinfunction "1_1") (pintype "passive"))
      (node (ref "RESET_BUTTON") (pin "1") (pinfunction "1_1") (pintype "passive"))
      (node (ref "RESET_BUTTON") (pin "2") (pinfunction "2_2") (pintype "passive"))
      (node (ref "SENSOR2") (pin "1") (pinfunction "GND_1") (pintype "power_in"))
      (node (ref "SENSOR2") (pin "5") (pinfunction "SDO_5") (pintype "bidirectional"))
      (node (ref "SENSOR2") (pin "7") (pinfunction "GND_7") (pintype "power_in"))
      (node (ref "SJ1") (pin "1") (pinfunction "1_1") (pintype "passive"))
      (node (ref "SUPERCAP") (pin "2") (pinfunction "2_2") (pintype "passive"))
      (node (ref "TP_GND") (pin "TP") (pinfunction "TP_TP") (pintype "input"))
      (node (ref "TP_GND1") (pin "TP") (pinfunction "TP_TP") (pintype "input"))
      (node (ref "U1") (pin "2") (pinfunction "VSS_2") (pintype "power_in"))
      (node (ref "U2") (pin "1") (pinfunction "GND_1") (pintype "power_in"))
      (node (ref "U2") (pin "28") (pinfunction "GND_28") (pintype "power_in"))
      (node (ref "U2") (pin "29_1") (pinfunction "GND_29_1") (pintype "power_in"))
      (node (ref "U2") (pin "29_2") (pinfunction "GND_29_2") (pintype "power_in"))
      (node (ref "U2") (pin "29_3") (pinfunction "GND_29_3") (pintype "power_in"))
      (node (ref "U2") (pin "29_4") (pinfunction "GND_29_4") (pintype "power_in"))
      (node (ref "U2") (pin "29_5") (pinfunction "GND_29_5") (pintype "power_in"))
      (node (ref "U2") (pin "29_6") (pinfunction "GND_29_6") (pintype "power_in"))
      (node (ref "U2") (pin "29_7") (pinfunction "GND_29_7") (pintype "power_in"))
      (node (ref "U2") (pin "29_8") (pinfunction "GND_29_8") (pintype "power_in"))
      (node (ref "U2") (pin "29_9") (pinfunction "GND_29_9") (pintype "power_in"))
      (node (ref "U4") (pin "1") (pinfunction "CTG_1") (pintype "power_in"))
      (node (ref "U4") (pin "4") (pinfunction "GND_4") (pintype "power_in"))
      (node (ref "U4") (pin "6") (pinfunction "QSTRT_6") (pintype "input"))
      (node (ref "U4") (pin "9") (pinfunction "EP_9") (pintype "power_in"))
      (node (ref "U5") (pin "13") (pinfunction "GND_13") (pintype "power_in"))
      (node (ref "U6") (pin "4") (pinfunction "GND_4") (pintype "power_in"))
      (node (ref "U6") (pin "9") (pinfunction "EXP_9") (pintype "passive"))
    )
    (net (code "15") (name "GPIO8") (class "Default")
      (node (ref "R10") (pin "1") (pinfunction "1_1") (pintype "passive"))
      (node (ref "U2") (pin "10") (pinfunction "IO8_10") (pintype "bidirectional"))
    )
    (net (code "16") (name "I2C_PW") (class "Default")
      (node (ref "C21") (pin "1") (pinfunction "1_1") (pintype "passive"))
      (node (ref "C22") (pin "1") (pinfunction "1_1") (pintype "passive"))
      (node (ref "R12_PINH") (pin "2") (pinfunction "2_2") (pintype "passive"))
      (node (ref "R13_PINH") (pin "2") (pinfunction "2_2") (pintype "passive"))
      (node (ref "SENSOR2") (pin "2") (pinfunction "CSB_2") (pintype "input"))
      (node (ref "SENSOR2") (pin "6") (pinfunction "VDDIO_6") (pintype "power_in"))
      (node (ref "SENSOR2") (pin "8") (pinfunction "VDD_8") (pintype "power_in"))
      (node (ref "U2") (pin "17") (pinfunction "IO19_17") (pintype "bidirectional"))
    )
    (net (code "17") (name "INT_RTC") (class "Default")
      (node (ref "R15_PINH1") (pin "1") (pinfunction "1_1") (pintype "passive"))
      (node (ref "TP_INT_RTC") (pin "TP") (pinfunction "TP_TP") (pintype "input"))
      (node (ref "U2") (pin "8") (pinfunction "IO0_8") (pintype "bidirectional"))
      (node (ref "U5") (pin "3") (pinfunction "SQW/~{INT}_3") (pintype "output"))
    )
    (net (code "18") (name "IO{slash}BOOT") (class "Default")
      (node (ref "BOOT_BUTTON") (pin "3") (pinfunction "3_3") (pintype "passive"))
      (node (ref "BOOT_BUTTON") (pin "4") (pinfunction "4_4") (pintype "passive"))
      (node (ref "C24") (pin "1") (pinfunction "1_1") (pintype "passive"))
      (node (ref "R_BOOT") (pin "1") (pinfunction "1_1") (pintype "passive"))
      (node (ref "U2") (pin "15") (pinfunction "IO9_15") (pintype "bidirectional"))
    )
    (net (code "19") (name "IO{slash}CHANGE") (class "Default")
      (node (ref "C25") (pin "1") (pinfunction "1_1") (pintype "passive"))
      (node (ref "CHANGE_BUTTON") (pin "3") (pinfunction "3_3") (pintype "passive"))
      (node (ref "CHANGE_BUTTON") (pin "4") (pinfunction "4_4") (pintype "passive"))
      (node (ref "R_CHANGE") (pin "1") (pinfunction "1_1") (pintype "passive"))
      (node (ref "U2") (pin "23") (pinfunction "IO15_23") (pintype "bidirectional"))
    )
    (net (code "20") (name "MISO") (class "Default")
      (node (ref "D7") (pin "1") (pinfunction "1_1") (pintype "passive"))
      (node (ref "J2") (pin "P7") (pinfunction "DAT0_P7") (pintype "bidirectional"))
      (node (ref "R16") (pin "1") (pinfunction "1_1") (pintype "passive"))
      (node (ref "TP_MISO") (pin "TP") (pinfunction "TP_TP") (pintype "input"))
      (node (ref "U2") (pin "27") (pinfunction "IO2_27") (pintype "bidirectional"))
      (node (ref "U6") (pin "2") (pinfunction "DO(IO1)_2") (pintype "bidirectional"))
    )
    (net (code "21") (name "MOSI") (class "Default")
      (node (ref "D8") (pin "1") (pinfunction "1_1") (pintype "passive"))
      (node (ref "J2") (pin "P3") (pinfunction "CMD_P3") (pintype "bidirectional"))
      (node (ref "J3") (pin "14") (pinfunction "14_14") (pintype "bidirectional"))
      (node (ref "R17") (pin "1") (pinfunction "1_1") (pintype "passive"))
      (node (ref "TP_MOSI") (pin "TP") (pinfunction "TP_TP") (pintype "input"))
      (node (ref "U2") (pin "7") (pinfunction "IO7_7") (pintype "bidirectional"))
      (node (ref "U6") (pin "5") (pinfunction "DI(IO0)_5") (pintype "bidirectional"))
    )
    (net (code "22") (name "Net-(CHG_LED-PadC)") (class "Default")
      (node (ref "CHG_LED") (pin "C") (pinfunction "C_C") (pintype "passive"))
      (node (ref "R8BAT") (pin "1") (pinfunction "1_1") (pintype "passive"))
    )
    (net (code "23") (name "Net-(D2-CATHODE)") (class "Default")
      (node (ref "C3BAT") (pin "1") (pinfunction "1_1") (pintype "passive"))
      (node (ref "D2") (pin "1") (pinfunction "CATHODE_1") (pintype "bidirectional"))
      (node (ref "IC1") (pin "1") (pinfunction "VIN_1") (pintype "bidirectional"))
      (node (ref "IC1") (pin "3") (pinfunction "CE_3") (pintype "bidirectional"))
      (node (ref "Q1") (pin "2") (pinfunction "S_2") (pintype "bidirectional"))
    )
    (net (code "24") (name "Net-(D4-K)") (class "Default")
      (node (ref "C8") (pin "1") (pinfunction "1_1") (pintype "passive"))
      (node (ref "D4") (pin "1") (pinfunction "K_1") (pintype "bidirectional"))
      (node (ref "D5") (pin "2") (pinfunction "A_2") (pintype "bidirectional"))
    )
    (net (code "25") (name "Net-(D6-CATHODE)") (class "Default")
      (node (ref "D6") (pin "1") (pinfunction "CATHODE_1") (pintype "bidirectional"))
      (node (ref "R_CAPACITOR") (pin "2") (pinfunction "2_2") (pintype "passive"))
    )
    (net (code "26") (name "Net-(EPD_C1-Pad2)") (class "Default")
      (node (ref "EPD_C1") (pin "2") (pinfunction "2_2") (pintype "passive"))
      (node (ref "J3") (pin "4") (pinfunction "4_4") (pintype "bidirectional"))
    )
    (net (code "27") (name "Net-(EPD_C2-Pad2)") (class "Default")
      (node (ref "EPD_C2") (pin "2") (pinfunction "2_2") (pintype "passive"))
      (node (ref "J3") (pin "5") (pinfunction "5_5") (pintype "bidirectional"))
    )
    (net (code "28") (name "Net-(EPD_C6-Pad2)") (class "Default")
      (node (ref "EPD_C6") (pin "2") (pinfunction "2_2") (pintype "passive"))
      (node (ref "J3") (pin "18") (pinfunction "18_18") (pintype "bidirectional"))
    )
    (net (code "29") (name "Net-(EPD_C7-Pad2)") (class "Default")
      (node (ref "EPD_C7") (pin "2") (pinfunction "2_2") (pintype "passive"))
      (node (ref "J3") (pin "19") (pinfunction "19_19") (pintype "bidirectional"))
    )
    (net (code "30") (name "Net-(EPD_C8-Pad2)") (class "Default")
      (node (ref "EPD_C8") (pin "2") (pinfunction "2_2") (pintype "passive"))
      (node (ref "J3") (pin "20") (pinfunction "20_20") (pintype "bidirectional"))
    )
    (net (code "31") (name "Net-(EPD_C10-Pad2)") (class "Default")
      (node (ref "EPD_C10") (pin "2") (pinfunction "2_2") (pintype "passive"))
      (node (ref "J3") (pin "22") (pinfunction "22_22") (pintype "bidirectional"))
    )
    (net (code "32") (name "Net-(EPD_C12-Pad2)") (class "Default")
      (node (ref "EPD_C12") (pin "2") (pinfunction "2_2") (pintype "passive"))
      (node (ref "J3") (pin "24") (pinfunction "24_24") (pintype "bidirectional"))
    )
    (net (code "33") (name "Net-(IC2-CT)") (class "Default")
      (node (ref "C_DELAY") (pin "1") (pinfunction "1_1") (pintype "passive"))
      (node (ref "IC2") (pin "5") (pinfunction "CT_5") (pintype "bidirectional"))
    )
    (net (code "34") (name "Net-(J1-PadA5)") (class "Default")
      (node (ref "J1") (pin "A5") (pinfunction "A5_A5") (pintype "bidirectional"))
      (node (ref "R2USB") (pin "2") (pinfunction "2_2") (pintype "passive"))
    )
    (net (code "35") (name "Net-(J1-PadB5)") (class "Default")
      (node (ref "J1") (pin "B5") (pinfunction "B5_B5") (pintype "bidirectional"))
      (node (ref "R3USB1") (pin "1") (pinfunction "1_1") (pintype "passive"))
    )
    (net (code "36") (name "Net-(U1-PROG)") (class "Default")
      (node (ref "R9BAT") (pin "2") (pinfunction "2_2") (pintype "passive"))
      (node (ref "U1") (pin "5") (pinfunction "PROG_5") (pintype "input"))
    )
    (net (code "37") (name "Net-(U1-STAT)") (class "Default")
      (node (ref "R8BAT") (pin "2") (pinfunction "2_2") (pintype "passive"))
      (node (ref "U1") (pin "1") (pinfunction "STAT_1") (pintype "output"))
    )
    (net (code "38") (name "PREVGH") (class "Default")
      (node (ref "D3") (pin "1") (pinfunction "K_1") (pintype "bidirectional"))
      (node (ref "EPD_C9") (pin "2") (pinfunction "2_2") (pintype "passive"))
      (node (ref "J3") (pin "21") (pinfunction "21_21") (pintype "bidirectional"))
    )
    (net (code "39") (name "PREVGL") (class "Default")
      (node (ref "D4") (pin "2") (pinfunction "A_2") (pintype "bidirectional"))
      (node (ref "EPD_C11") (pin "2") (pinfunction "2_2") (pintype "passive"))
      (node (ref "J3") (pin "23") (pinfunction "23_23") (pintype "bidirectional"))
    )
    (net (code "40") (name "RESE") (class "Default")
      (node (ref "J3") (pin "3") (pinfunction "3_3") (pintype "bidirectional"))
      (node (ref "Q2") (pin "2") (pinfunction "S_2") (pintype "bidirectional"))
      (node (ref "R7") (pin "2") (pinfunction "2_2") (pintype "passive"))
    )
    (net (code "41") (name "RESE'") (class "Default")
      (node (ref "R5") (pin "2") (pinfunction "2_2") (pintype "passive"))
      (node (ref "R7") (pin "1") (pinfunction "1_1") (pintype "passive"))
      (node (ref "SJ1") (pin "2") (pinfunction "2_2") (pintype "passive"))
    )
    (net (code "42") (name "RESET") (class "Default")
      (node (ref "C23") (pin "1") (pinfunction "1_1") (pintype "passive"))
      (node (ref "IC2") (pin "1") (pinfunction "VOUT_1") (pintype "bidirectional"))
      (node (ref "RESET_BUTTON") (pin "3") (pinfunction "3_3") (pintype "passive"))
      (node (ref "RESET_BUTTON") (pin "4") (pinfunction "4_4") (pintype "passive"))
      (node (ref "R_RESET") (pin "1") (pinfunction "1_1") (pintype "passive"))
      (node (ref "U2") (pin "3") (pinfunction "EN_3") (pintype "input"))
    )
    (net (code "43") (name "RTC_RST") (class "Default")
      (node (ref "U2") (pin "16") (pinfunction "IO18_16") (pintype "bidirectional"))
      (node (ref "U5") (pin "4") (pinfunction "~{RST}_4") (pintype "input"))
    )
    (net (code "44") (name "RX") (class "Default")
      (node (ref "TP_RX") (pin "TP") (pinfunction "TP_TP") (pintype "input"))
      (node (ref "U2") (pin "24") (pinfunction "RXD0/GPIO17_24") (pintype "bidirectional"))
    )
    (net (code "45") (name "SCK") (class "Default")
      (node (ref "D9") (pin "1") (pinfunction "1_1") (pintype "passive"))
      (node (ref "J2") (pin "P5") (pinfunction "CLK_P5") (pintype "bidirectional"))
      (node (ref "J3") (pin "13") (pinfunction "13_13") (pintype "bidirectional"))
      (node (ref "R18") (pin "1") (pinfunction "1_1") (pintype "passive"))
      (node (ref "TP_SCK") (pin "TP") (pinfunction "TP_TP") (pintype "input"))
      (node (ref "U2") (pin "6") (pinfunction "IO6_6") (pintype "bidirectional"))
      (node (ref "U6") (pin "6") (pinfunction "CLK_6") (pintype "input"))
    )
    (net (code "46") (name "SCL") (class "Default")
      (node (ref "J4") (pin "4") (pinfunction "4_4") (pintype "passive"))
      (node (ref "R12_PINH") (pin "1") (pinfunction "1_1") (pintype "passive"))
      (node (ref "SENSOR2") (pin "4") (pinfunction "SCK_4") (pintype "input"))
      (node (ref "U2") (pin "20") (pinfunction "IO22_20") (pintype "bidirectional"))
      (node (ref "U4") (pin "7") (pinfunction "SCL_7") (pintype "input"))
      (node (ref "U5") (pin "16") (pinfunction "SCL_16") (pintype "input"))
    )
    (net (code "47") (name "SDA") (class "Default")
      (node (ref "J4") (pin "3") (pinfunction "3_3") (pintype "passive"))
      (node (ref "R13_PINH") (pin "1") (pinfunction "1_1") (pintype "passive"))
      (node (ref "SENSOR2") (pin "3") (pinfunction "SDI_3") (pintype "bidirectional"))
      (node (ref "U2") (pin "19") (pinfunction "IO21_19") (pintype "bidirectional"))
      (node (ref "U4") (pin "8") (pinfunction "SDA_8") (pintype "bidirectional"))
      (node (ref "U5") (pin "15") (pinfunction "SDA_15") (pintype "bidirectional"))
    )
    (net (code "48") (name "SRC") (class "Default")
      (node (ref "C8") (pin "2") (pinfunction "2_2") (pintype "passive"))
      (node (ref "D3") (pin "2") (pinfunction "A_2") (pintype "bidirectional"))
      (node (ref "L2") (pin "1") (pinfunction "1_1") (pintype "passive"))
      (node (ref "Q2") (pin "3") (pinfunction "D_3") (pintype "bidirectional"))
    )
    (net (code "49") (name "SS_SD") (class "Default")
      (node (ref "D12") (pin "1") (pinfunction "1_1") (pintype "passive"))
      (node (ref "J2") (pin "P2") (pinfunction "CD/DAT3_P2") (pintype "bidirectional"))
      (node (ref "R21") (pin "1") (pinfunction "1_1") (pintype "passive"))
      (node (ref "U2") (pin "4") (pinfunction "IO4_4") (pintype "bidirectional"))
    )
    (net (code "50") (name "TX") (class "Default")
      (node (ref "TP_TX") (pin "TP") (pinfunction "TP_TP") (pintype "input"))
      (node (ref "U2") (pin "25") (pinfunction "TXD0/GPIO16_25") (pintype "bidirectional"))
    )
    (net (code "51") (name "USB_D+") (class "Default")
      (node (ref "D1") (pin "1") (pinfunction "I/O1_1_1") (pintype "bidirectional"))
      (node (ref "U2") (pin "14") (pinfunction "IO13_14") (pintype "bidirectional"))
    )
    (net (code "52") (name "USB_D-") (class "Default")
      (node (ref "D1") (pin "3") (pinfunction "I/O2_1_3") (pintype "bidirectional"))
      (node (ref "U2") (pin "13") (pinfunction "IO12_13") (pintype "bidirectional"))
    )
    (net (code "53") (name "VBAT") (class "Default")
      (node (ref "C10BAT") (pin "1") (pinfunction "1_1") (pintype "passive"))
      (node (ref "Q1") (pin "3") (pinfunction "D_3") (pintype "bidirectional"))
      (node (ref "TP_VBAT") (pin "TP") (pinfunction "TP_TP") (pintype "input"))
      (node (ref "U1") (pin "3") (pinfunction "VBAT_3") (pintype "power_in"))
      (node (ref "U4") (pin "2") (pinfunction "CELL_2") (pintype "power_in"))
      (node (ref "U4") (pin "3") (pinfunction "VDD_3") (pintype "power_in"))
    )
    (net (code "54") (name "VBUS") (class "Default")
      (node (ref "C1USB") (pin "1") (pinfunction "1_1") (pintype "passive"))
      (node (ref "C2USB1") (pin "1") (pinfunction "1_1") (pintype "passive"))
      (node (ref "C9BAT") (pin "1") (pinfunction "1_1") (pintype "passive"))
      (node (ref "CHG_LED") (pin "A") (pinfunction "A_A") (pintype "passive"))
      (node (ref "D1") (pin "5") (pinfunction "VBUS_5") (pintype "bidirectional"))
      (node (ref "D2") (pin "2") (pinfunction "ANODE_2") (pintype "bidirectional"))
      (node (ref "Q1") (pin "1") (pinfunction "G_1") (pintype "bidirectional"))
      (node (ref "R1") (pin "2") (pinfunction "2_2") (pintype "passive"))
      (node (ref "R4PWRUSB1") (pin "2") (pinfunction "2_2") (pintype "passive"))
      (node (ref "TP_VBUS") (pin "TP") (pinfunction "TP_TP") (pintype "input"))
      (node (ref "U1") (pin "4") (pinfunction "VIN_4") (pintype "power_in"))
    )
    (net (code "55") (name "VRTC") (class "Default")
      (node (ref "C26") (pin "1") (pinfunction "1_1") (pintype "passive"))
      (node (ref "R_CAPACITOR") (pin "1") (pinfunction "1_1") (pintype "passive"))
      (node (ref "SUPERCAP") (pin "1") (pinfunction "1_1") (pintype "passive"))
      (node (ref "U5") (pin "14") (pinfunction "VBAT_14") (pintype "power_in"))
    )
    (net (code "56") (name "unconnected-(IC1-NC-Pad4)") (class "Default")
      (node (ref "IC1") (pin "4") (pinfunction "NC_4") (pintype "no_connect"))
    )
    (net (code "57") (name "unconnected-(IC2-NC-Pad4)") (class "Default")
      (node (ref "IC2") (pin "4") (pinfunction "NC_4") (pintype "no_connect"))
    )
    (net (code "58") (name "unconnected-(J1-PadA8)") (class "Default")
      (node (ref "J1") (pin "A8") (pinfunction "A8_A8") (pintype "bidirectional"))
    )
    (net (code "59") (name "unconnected-(J1-PadB8)") (class "Default")
      (node (ref "J1") (pin "B8") (pinfunction "B8_B8") (pintype "bidirectional"))
    )
    (net (code "60") (name "unconnected-(J2-DAT1-PadP8)") (class "Default")
      (node (ref "J2") (pin "P8") (pinfunction "DAT1_P8") (pintype "bidirectional"))
    )
    (net (code "61") (name "unconnected-(J2-DAT2-PadP1)") (class "Default")
      (node (ref "J2") (pin "P1") (pinfunction "DAT2_P1") (pintype "bidirectional"))
    )
    (net (code "62") (name "unconnected-(J2-DETECTION_1-PadS1)") (class "Default")
      (node (ref "J2") (pin "S1") (pinfunction "DETECTION_1_S1") (pintype "bidirectional"))
    )
    (net (code "63") (name "unconnected-(J2-DETECTION_2-PadS2)") (class "Default")
      (node (ref "J2") (pin "S2") (pinfunction "DETECTION_2_S2") (pintype "bidirectional"))
    )
    (net (code "64") (name "unconnected-(J3-Pad1)") (class "Default")
      (node (ref "J3") (pin "1") (pinfunction "1_1") (pintype "bidirectional"))
    )
    (net (code "65") (name "unconnected-(J3-Pad6)") (class "Default")
      (node (ref "J3") (pin "6") (pinfunction "6_6") (pintype "bidirectional"))
    )
    (net (code "66") (name "unconnected-(J3-Pad7)") (class "Default")
      (node (ref "J3") (pin "7") (pinfunction "7_7") (pintype "bidirectional"))
    )
    (net (code "67") (name "unconnected-(U2-NC-Pad22)") (class "Default")
      (node (ref "U2") (pin "22") (pinfunction "NC_22") (pintype "no_connect"))
    )
    (net (code "68") (name "unconnected-(U4-~{ALERT}-Pad5)") (class "Default")
      (node (ref "U4") (pin "5") (pinfunction "~{ALERT}_5") (pintype "output"))
    )
  )
)
